# TinyAPRS-mini.net
KiCad netlist of a schematic drawn in EAGLE
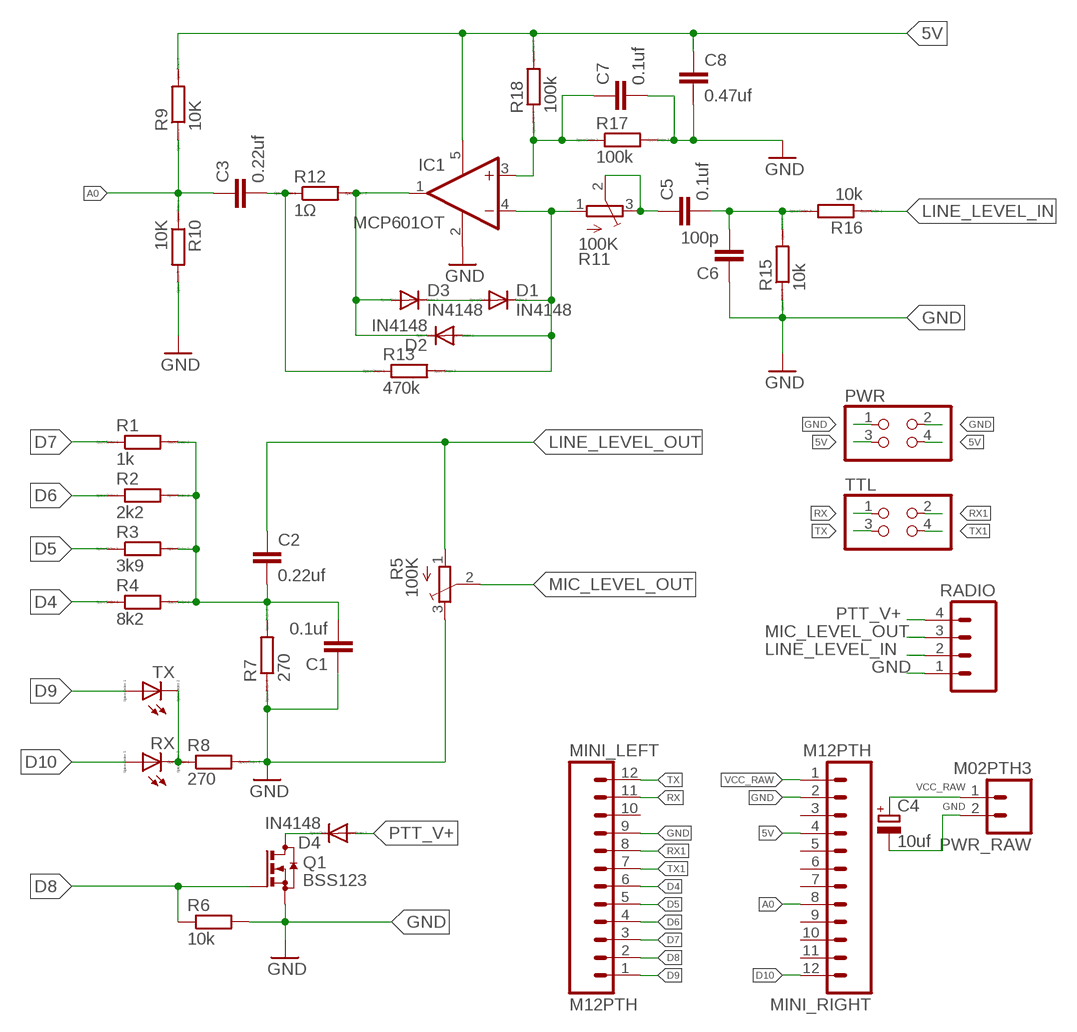
[diagram p0: schematic, sheet 1]

(export (version "E")
  (design (tool "Eeschema 10.0.6"))
  (components
    (comp (ref "C1")
      (value "0.1uf")
      (footprint "eagle-import:C050-024X044")
      (libsource (lib "eagle-import") (part "C-EU050-024X044"))
    )
    (comp (ref "C2")
      (value "0.22uf")
      (footprint "eagle-import:C050-024X044")
      (libsource (lib "eagle-import") (part "C-EU050-024X044"))
    )
    (comp (ref "C3")
      (value "0.22uf")
      (footprint "eagle-import:C050-024X044")
      (libsource (lib "eagle-import") (part "C-EU050-024X044"))
    )
    (comp (ref "C4")
      (value "10uf")
      (footprint "eagle-import:E2,5-5")
      (libsource (lib "eagle-import") (part "CPOL-EUE2.5-5"))
    )
    (comp (ref "C5")
      (value "0.1uf")
      (footprint "eagle-import:C050-024X044")
      (libsource (lib "eagle-import") (part "C-EU050-024X044"))
    )
    (comp (ref "C6")
      (value "100p")
      (footprint "eagle-import:C050-024X044")
      (libsource (lib "eagle-import") (part "C-EU050-024X044"))
    )
    (comp (ref "C7")
      (value "0.1uf")
      (footprint "eagle-import:C050-024X044")
      (libsource (lib "eagle-import") (part "C-EU050-024X044"))
    )
    (comp (ref "C8")
      (value "0.47uf")
      (footprint "eagle-import:C050-024X044")
      (libsource (lib "eagle-import") (part "C-EU050-024X044"))
    )
    (comp (ref "D1")
      (value "IN4148")
      (footprint "eagle-import:D-2.5")
      (libsource (lib "eagle-import") (part "DIODE-D-2.5"))
    )
    (comp (ref "D2")
      (value "IN4148")
      (footprint "eagle-import:D-2.5")
      (libsource (lib "eagle-import") (part "DIODE-D-2.5"))
    )
    (comp (ref "D3")
      (value "IN4148")
      (footprint "eagle-import:D-2.5")
      (libsource (lib "eagle-import") (part "DIODE-D-2.5"))
    )
    (comp (ref "D4")
      (value "IN4148")
      (footprint "eagle-import:D-2.5")
      (libsource (lib "eagle-import") (part "DIODE-D-2.5"))
    )
    (comp (ref "IC1")
      (value "MCP601OT")
      (footprint "eagle-import:SOT23-5")
      (libsource (lib "eagle-import") (part "MCP601OT"))
    )
    (comp (ref "MINI_LEFT")
      (value "M12PTH")
      (footprint "eagle-import:1X12")
      (libsource (lib "eagle-import") (part "M12PTH"))
    )
    (comp (ref "MINI_RIGHT")
      (value "M12PTH")
      (footprint "eagle-import:1X12")
      (libsource (lib "eagle-import") (part "M12PTH"))
    )
    (comp (ref "PWR")
      (value "PINHD-2X2")
      (footprint "eagle-import:2X02")
      (libsource (lib "eagle-import") (part "PINHD-2X2"))
    )
    (comp (ref "PWR_RAW")
      (value "M02PTH3")
      (footprint "eagle-import:1X02_LONGPADS")
      (libsource (lib "eagle-import") (part "M02PTH3"))
    )
    (comp (ref "Q1")
      (value "BSS123")
      (footprint "eagle-import:SOT23")
      (libsource (lib "eagle-import") (part "BSS123"))
    )
    (comp (ref "R1")
      (value "1k")
      (footprint "eagle-import:0204_5")
      (libsource (lib "eagle-import") (part "R-EU_0204_5"))
    )
    (comp (ref "R2")
      (value "2k2")
      (footprint "eagle-import:0204_5")
      (libsource (lib "eagle-import") (part "R-EU_0204_5"))
    )
    (comp (ref "R3")
      (value "3k9")
      (footprint "eagle-import:0204_5")
      (libsource (lib "eagle-import") (part "R-EU_0204_5"))
    )
    (comp (ref "R4")
      (value "8k2")
      (footprint "eagle-import:0204_5")
      (libsource (lib "eagle-import") (part "R-EU_0204_5"))
    )
    (comp (ref "R5")
      (value "100K")
      (footprint "eagle-import:TC33X")
      (libsource (lib "eagle-import") (part "TRIMPOTTC33X"))
    )
    (comp (ref "R6")
      (value "10k")
      (footprint "eagle-import:0204_5")
      (libsource (lib "eagle-import") (part "R-EU_0204/5"))
    )
    (comp (ref "R7")
      (value "270")
      (footprint "eagle-import:0204_5")
      (libsource (lib "eagle-import") (part "R-EU_0204_5"))
    )
    (comp (ref "R8")
      (value "270")
      (footprint "eagle-import:0204V")
      (libsource (lib "eagle-import") (part "R-EU_0204_2V"))
    )
    (comp (ref "R9")
      (value "10K")
      (footprint "eagle-import:0204_5")
      (libsource (lib "eagle-import") (part "R-EU_0204_5"))
    )
    (comp (ref "R10")
      (value "10K")
      (footprint "eagle-import:0204_5")
      (libsource (lib "eagle-import") (part "R-EU_0204_5"))
    )
    (comp (ref "R11")
      (value "100K")
      (footprint "eagle-import:TC33X")
      (libsource (lib "eagle-import") (part "TRIMPOTTC33X"))
    )
    (comp (ref "R12")
      (value "1Ω")
      (footprint "eagle-import:0204V")
      (libsource (lib "eagle-import") (part "R-EU_0204_2V"))
    )
    (comp (ref "R13")
      (value "470k")
      (footprint "eagle-import:0204_5")
      (libsource (lib "eagle-import") (part "R-EU_0204_5"))
    )
    (comp (ref "R15")
      (value "10k")
      (footprint "eagle-import:0204_5")
      (libsource (lib "eagle-import") (part "R-EU_0204_5"))
    )
    (comp (ref "R16")
      (value "10k")
      (footprint "eagle-import:0204_5")
      (libsource (lib "eagle-import") (part "R-EU_0204_5"))
    )
    (comp (ref "R17")
      (value "100k")
      (footprint "eagle-import:0204_5")
      (libsource (lib "eagle-import") (part "R-EU_0204_5"))
    )
    (comp (ref "R18")
      (value "100k")
      (footprint "eagle-import:0204_5")
      (libsource (lib "eagle-import") (part "R-EU_0204_5"))
    )
    (comp (ref "RADIO")
      (value "M04PTH")
      (footprint "eagle-import:1X04")
      (libsource (lib "eagle-import") (part "M04PTH"))
    )
    (comp (ref "RX")
      (value "LED_ELD260")
      (footprint "eagle-import:LED_LD260")
      (libsource (lib "eagle-import") (part "LED_ELD260"))
    )
    (comp (ref "TTL")
      (value "PINHD-2X2")
      (footprint "eagle-import:2X02")
      (libsource (lib "eagle-import") (part "PINHD-2X2"))
    )
    (comp (ref "TX")
      (value "LED_ELD260")
      (footprint "eagle-import:LED_LD260")
      (libsource (lib "eagle-import") (part "LED_ELD260"))
    )
  )
  (nets
    (net (code "1") (name "5V") (class "Default")
      (node (ref "C8") (pin "1") (pinfunction "1_1") (pintype "passive"))
      (node (ref "IC1") (pin "5") (pinfunction "V+_5") (pintype "power_in"))
      (node (ref "MINI_RIGHT") (pin "4") (pinfunction "4_4") (pintype "passive"))
      (node (ref "PWR") (pin "3") (pinfunction "3_3") (pintype "passive"))
      (node (ref "PWR") (pin "4") (pinfunction "4_4") (pintype "passive"))
      (node (ref "R18") (pin "2") (pinfunction "2_2") (pintype "passive"))
      (node (ref "R9") (pin "2") (pinfunction "2_2") (pintype "passive"))
    )
    (net (code "2") (name "A0") (class "Default")
      (node (ref "C3") (pin "1") (pinfunction "1_1") (pintype "passive"))
      (node (ref "MINI_RIGHT") (pin "8") (pinfunction "8_8") (pintype "passive"))
      (node (ref "R10") (pin "1") (pinfunction "1_1") (pintype "passive"))
      (node (ref "R9") (pin "1") (pinfunction "1_1") (pintype "passive"))
    )
    (net (code "3") (name "D4") (class "Default")
      (node (ref "MINI_LEFT") (pin "6") (pinfunction "6_6") (pintype "passive"))
      (node (ref "R4") (pin "1") (pinfunction "1_1") (pintype "passive"))
    )
    (net (code "4") (name "D5") (class "Default")
      (node (ref "MINI_LEFT") (pin "5") (pinfunction "5_5") (pintype "passive"))
      (node (ref "R3") (pin "1") (pinfunction "1_1") (pintype "passive"))
    )
    (net (code "5") (name "D6") (class "Default")
      (node (ref "MINI_LEFT") (pin "4") (pinfunction "4_4") (pintype "passive"))
      (node (ref "R2") (pin "1") (pinfunction "1_1") (pintype "passive"))
    )
    (net (code "6") (name "D7") (class "Default")
      (node (ref "MINI_LEFT") (pin "3") (pinfunction "3_3") (pintype "passive"))
      (node (ref "R1") (pin "1") (pinfunction "1_1") (pintype "passive"))
    )
    (net (code "7") (name "D8") (class "Default")
      (node (ref "MINI_LEFT") (pin "2") (pinfunction "2_2") (pintype "passive"))
      (node (ref "Q1") (pin "1") (pinfunction "G_1") (pintype "passive"))
      (node (ref "R6") (pin "1") (pinfunction "1_1") (pintype "passive"))
    )
    (net (code "8") (name "D9") (class "Default")
      (node (ref "MINI_LEFT") (pin "1") (pinfunction "1_1") (pintype "passive"))
      (node (ref "TX") (pin "A") (pinfunction "A_A") (pintype "passive"))
    )
    (net (code "9") (name "D10") (class "Default")
      (node (ref "MINI_RIGHT") (pin "12") (pinfunction "12_12") (pintype "passive"))
      (node (ref "RX") (pin "A") (pinfunction "A_A") (pintype "passive"))
    )
    (net (code "10") (name "GND") (class "Default")
      (node (ref "C1") (pin "1") (pinfunction "1_1") (pintype "passive"))
      (node (ref "C4") (pin "-") (pinfunction "-_-") (pintype "passive"))
      (node (ref "C6") (pin "1") (pinfunction "1_1") (pintype "passive"))
      (node (ref "C7") (pin "2") (pinfunction "2_2") (pintype "passive"))
      (node (ref "C8") (pin "2") (pinfunction "2_2") (pintype "passive"))
      (node (ref "IC1") (pin "2") (pinfunction "V-_2") (pintype "power_in"))
      (node (ref "MINI_LEFT") (pin "9") (pinfunction "9_9") (pintype "passive"))
      (node (ref "MINI_RIGHT") (pin "2") (pinfunction "2_2") (pintype "passive"))
      (node (ref "PWR") (pin "1") (pinfunction "1_1") (pintype "passive"))
      (node (ref "PWR") (pin "2") (pinfunction "2_2") (pintype "passive"))
      (node (ref "PWR_RAW") (pin "2") (pinfunction "2_2") (pintype "passive"))
      (node (ref "Q1") (pin "2") (pinfunction "S_2") (pintype "passive"))
      (node (ref "R10") (pin "2") (pinfunction "2_2") (pintype "passive"))
      (node (ref "R15") (pin "1") (pinfunction "1_1") (pintype "passive"))
      (node (ref "R17") (pin "2") (pinfunction "2_2") (pintype "passive"))
      (node (ref "R5") (pin "3") (pinfunction "E_3") (pintype "passive"))
      (node (ref "R6") (pin "2") (pinfunction "2_2") (pintype "passive"))
      (node (ref "R7") (pin "1") (pinfunction "1_1") (pintype "passive"))
      (node (ref "R8") (pin "2") (pinfunction "2_2") (pintype "passive"))
      (node (ref "RADIO") (pin "1") (pinfunction "1_1") (pintype "passive"))
    )
    (net (code "11") (name "LINE_LEVEL_IN") (class "Default")
      (node (ref "R16") (pin "1") (pinfunction "1_1") (pintype "passive"))
      (node (ref "RADIO") (pin "2") (pinfunction "2_2") (pintype "passive"))
    )
    (net (code "12") (name "LINE_LEVEL_OUT") (class "Default")
      (node (ref "C2") (pin "1") (pinfunction "1_1") (pintype "passive"))
      (node (ref "R5") (pin "1") (pinfunction "A_1") (pintype "passive"))
    )
    (net (code "13") (name "MIC_LEVEL_OUT") (class "Default")
      (node (ref "R5") (pin "2") (pinfunction "S_2") (pintype "passive"))
      (node (ref "RADIO") (pin "3") (pinfunction "3_3") (pintype "passive"))
    )
    (net (code "14") (name "Net-(C1-Pad2)") (class "Default")
      (node (ref "C1") (pin "2") (pinfunction "2_2") (pintype "passive"))
      (node (ref "C2") (pin "2") (pinfunction "2_2") (pintype "passive"))
      (node (ref "R1") (pin "2") (pinfunction "2_2") (pintype "passive"))
      (node (ref "R2") (pin "2") (pinfunction "2_2") (pintype "passive"))
      (node (ref "R3") (pin "2") (pinfunction "2_2") (pintype "passive"))
      (node (ref "R4") (pin "2") (pinfunction "2_2") (pintype "passive"))
      (node (ref "R7") (pin "2") (pinfunction "2_2") (pintype "passive"))
    )
    (net (code "15") (name "Net-(C3-Pad2)") (class "Default")
      (node (ref "C3") (pin "2") (pinfunction "2_2") (pintype "passive"))
      (node (ref "R12") (pin "1") (pinfunction "1_1") (pintype "passive"))
      (node (ref "R13") (pin "1") (pinfunction "1_1") (pintype "passive"))
    )
    (net (code "16") (name "Net-(C5-Pad2)") (class "Default")
      (node (ref "C5") (pin "2") (pinfunction "2_2") (pintype "passive"))
      (node (ref "C6") (pin "2") (pinfunction "2_2") (pintype "passive"))
      (node (ref "R15") (pin "2") (pinfunction "2_2") (pintype "passive"))
      (node (ref "R16") (pin "2") (pinfunction "2_2") (pintype "passive"))
    )
    (net (code "17") (name "Net-(D1-PadA)") (class "Default")
      (node (ref "D1") (pin "A") (pinfunction "A_A") (pintype "passive"))
      (node (ref "D3") (pin "C") (pinfunction "C_C") (pintype "passive"))
    )
    (net (code "18") (name "Net-(IC1-+IN)") (class "Default")
      (node (ref "C7") (pin "1") (pinfunction "1_1") (pintype "passive"))
      (node (ref "IC1") (pin "3") (pinfunction "+IN_3") (pintype "input"))
      (node (ref "R17") (pin "1") (pinfunction "1_1") (pintype "passive"))
      (node (ref "R18") (pin "1") (pinfunction "1_1") (pintype "passive"))
    )
    (net (code "19") (name "Net-(IC1--IN)") (class "Default")
      (node (ref "D1") (pin "C") (pinfunction "C_C") (pintype "passive"))
      (node (ref "D2") (pin "A") (pinfunction "A_A") (pintype "passive"))
      (node (ref "IC1") (pin "4") (pinfunction "-IN_4") (pintype "input"))
      (node (ref "R11") (pin "1") (pinfunction "A_1") (pintype "passive"))
      (node (ref "R13") (pin "2") (pinfunction "2_2") (pintype "passive"))
    )
    (net (code "20") (name "Net-(IC1-OUT)") (class "Default")
      (node (ref "D2") (pin "C") (pinfunction "C_C") (pintype "passive"))
      (node (ref "D3") (pin "A") (pinfunction "A_A") (pintype "passive"))
      (node (ref "IC1") (pin "1") (pinfunction "OUT_1") (pintype "output"))
      (node (ref "R12") (pin "2") (pinfunction "2_2") (pintype "passive"))
    )
    (net (code "21") (name "Net-(Q1-D)") (class "Default")
      (node (ref "D4") (pin "C") (pinfunction "C_C") (pintype "passive"))
      (node (ref "Q1") (pin "3") (pinfunction "D_3") (pintype "passive"))
    )
    (net (code "22") (name "Net-(R11-E)") (class "Default")
      (node (ref "C5") (pin "1") (pinfunction "1_1") (pintype "passive"))
      (node (ref "R11") (pin "2") (pinfunction "S_2") (pintype "passive"))
      (node (ref "R11") (pin "3") (pinfunction "E_3") (pintype "passive"))
    )
    (net (code "23") (name "Net-(RX-C)") (class "Default")
      (node (ref "R8") (pin "1") (pinfunction "1_1") (pintype "passive"))
      (node (ref "RX") (pin "K") (pinfunction "C_K") (pintype "passive"))
      (node (ref "TX") (pin "K") (pinfunction "C_K") (pintype "passive"))
    )
    (net (code "24") (name "PTT_V+") (class "Default")
      (node (ref "D4") (pin "A") (pinfunction "A_A") (pintype "passive"))
      (node (ref "RADIO") (pin "4") (pinfunction "4_4") (pintype "passive"))
    )
    (net (code "25") (name "RX") (class "Default")
      (node (ref "MINI_LEFT") (pin "11") (pinfunction "11_11") (pintype "passive"))
      (node (ref "TTL") (pin "1") (pinfunction "1_1") (pintype "passive"))
    )
    (net (code "26") (name "RX1") (class "Default")
      (node (ref "MINI_LEFT") (pin "8") (pinfunction "8_8") (pintype "passive"))
      (node (ref "TTL") (pin "2") (pinfunction "2_2") (pintype "passive"))
    )
    (net (code "27") (name "TX") (class "Default")
      (node (ref "MINI_LEFT") (pin "12") (pinfunction "12_12") (pintype "passive"))
      (node (ref "TTL") (pin "3") (pinfunction "3_3") (pintype "passive"))
    )
    (net (code "28") (name "TX1") (class "Default")
      (node (ref "MINI_LEFT") (pin "7") (pinfunction "7_7") (pintype "passive"))
      (node (ref "TTL") (pin "4") (pinfunction "4_4") (pintype "passive"))
    )
    (net (code "29") (name "VCC_RAW") (class "Default")
      (node (ref "C4") (pin "+") (pinfunction "+_+") (pintype "passive"))
      (node (ref "MINI_RIGHT") (pin "1") (pinfunction "1_1") (pintype "passive"))
      (node (ref "PWR_RAW") (pin "1") (pinfunction "1_1") (pintype "passive"))
    )
    (net (code "30") (name "unconnected-(MINI_LEFT-Pad10)") (class "Default")
      (node (ref "MINI_LEFT") (pin "10") (pinfunction "10_10") (pintype "passive"))
    )
    (net (code "31") (name "unconnected-(MINI_RIGHT-Pad3)") (class "Default")
      (node (ref "MINI_RIGHT") (pin "3") (pinfunction "3_3") (pintype "passive"))
    )
    (net (code "32") (name "unconnected-(MINI_RIGHT-Pad5)") (class "Default")
      (node (ref "MINI_RIGHT") (pin "5") (pinfunction "5_5") (pintype "passive"))
    )
    (net (code "33") (name "unconnected-(MINI_RIGHT-Pad6)") (class "Default")
      (node (ref "MINI_RIGHT") (pin "6") (pinfunction "6_6") (pintype "passive"))
    )
    (net (code "34") (name "unconnected-(MINI_RIGHT-Pad7)") (class "Default")
      (node (ref "MINI_RIGHT") (pin "7") (pinfunction "7_7") (pintype "passive"))
    )
    (net (code "35") (name "unconnected-(MINI_RIGHT-Pad9)") (class "Default")
      (node (ref "MINI_RIGHT") (pin "9") (pinfunction "9_9") (pintype "passive"))
    )
    (net (code "36") (name "unconnected-(MINI_RIGHT-Pad10)") (class "Default")
      (node (ref "MINI_RIGHT") (pin "10") (pinfunction "10_10") (pintype "passive"))
    )
    (net (code "37") (name "unconnected-(MINI_RIGHT-Pad11)") (class "Default")
      (node (ref "MINI_RIGHT") (pin "11") (pinfunction "11_11") (pintype "passive"))
    )
  )
)
